# Schematic.net
KiCad netlist of a schematic drawn in EAGLE
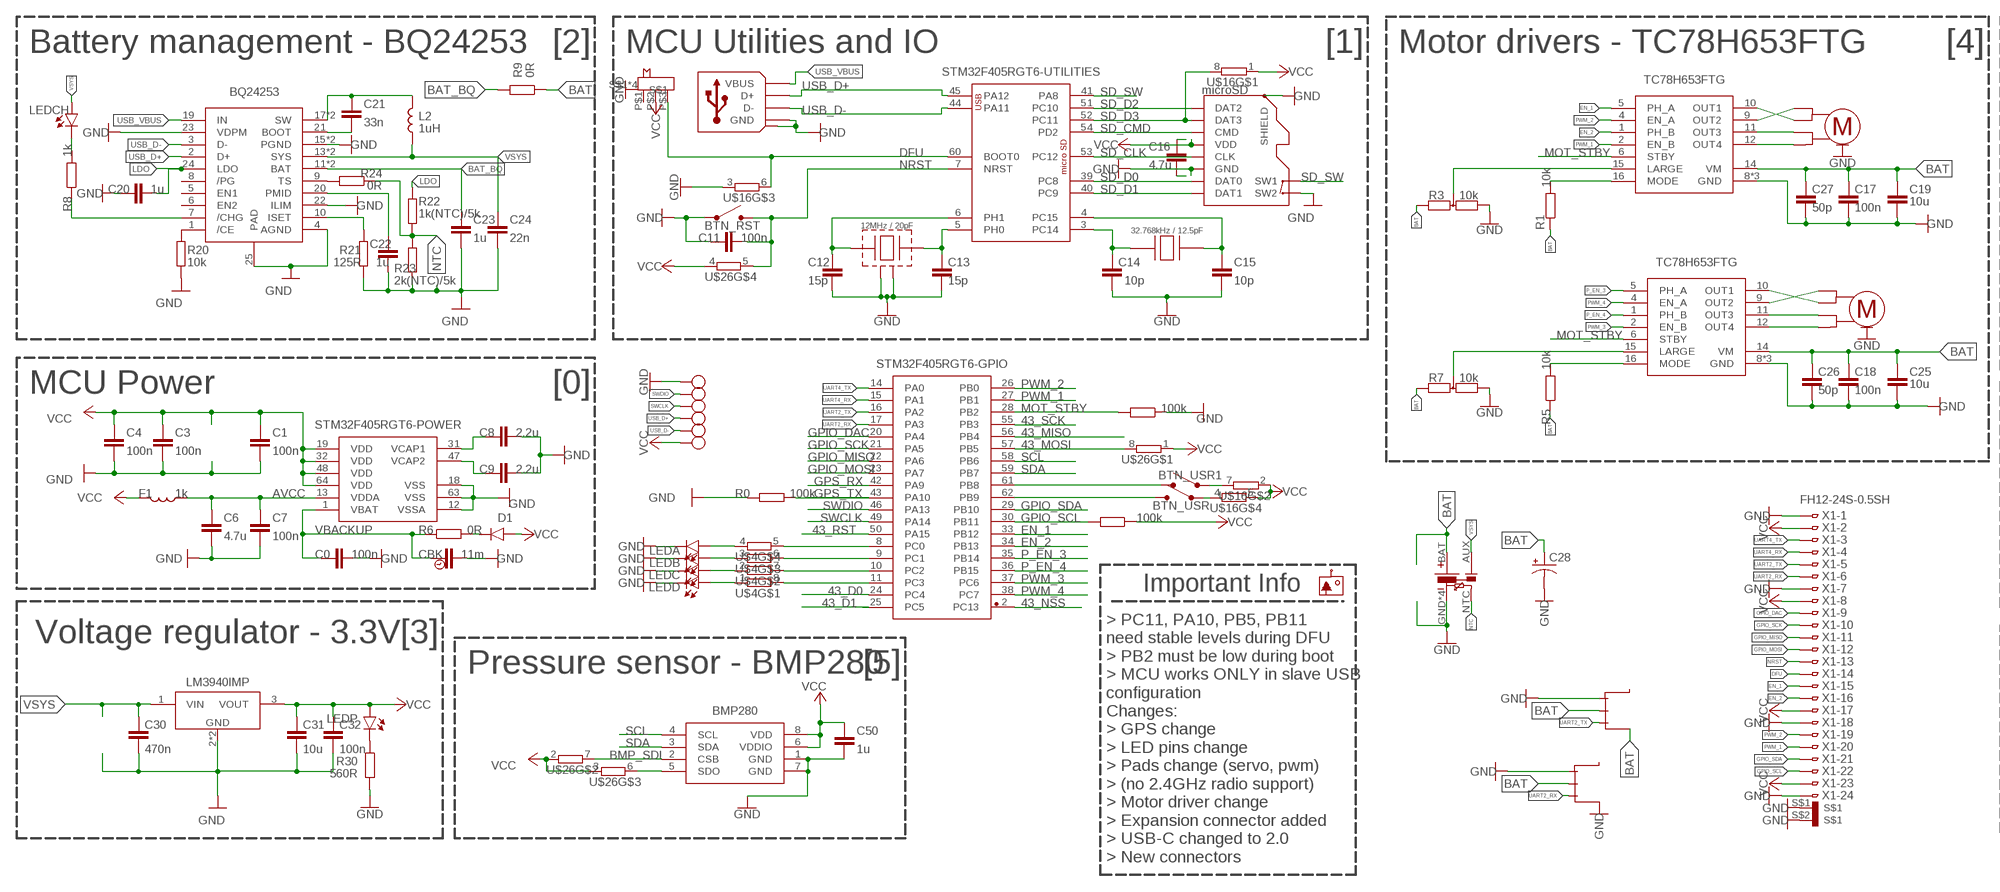
[diagram p0: schematic, sheet 1, part 1 of 2]
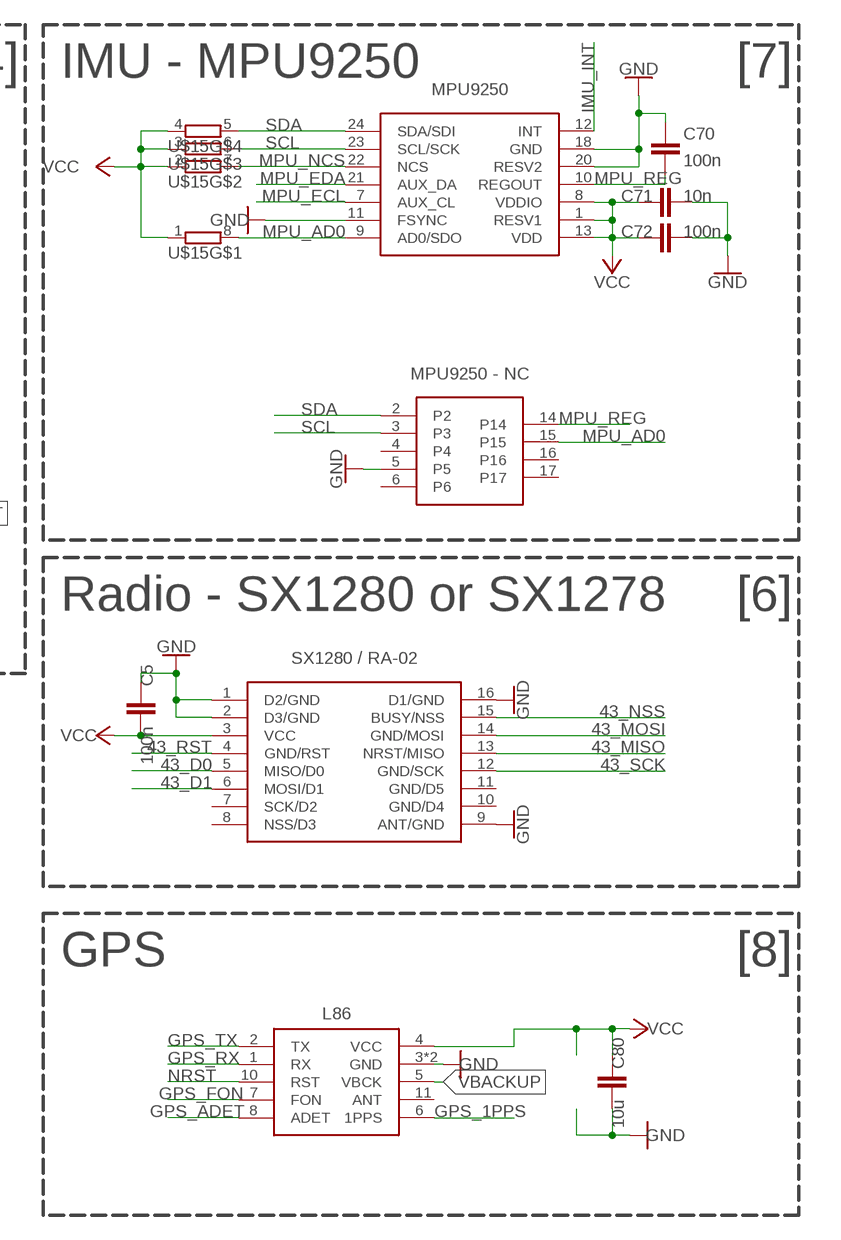
[diagram p1: schematic, sheet 1, part 2 of 2]

(export (version "E")
  (design (tool "Eeschema 10.0.6"))
  (components
    (comp (ref "BTN_DFU")
      (value "SLIDE-SWITCH2")
      (footprint "eagle-import:SLIDE-SWITCH-2")
      (libsource (lib "eagle-import") (part "SLIDE-SWITCH2"))
    )
    (comp (ref "BTN_RST")
      (value "PUSH-SWITCH")
      (footprint "eagle-import:SWITCH_SMD")
      (libsource (lib "eagle-import") (part "PUSH-SWITCH"))
    )
    (comp (ref "BTN_USR")
      (value "PUSH-SWITCH")
      (footprint "eagle-import:SWITCH_SMD")
      (libsource (lib "eagle-import") (part "PUSH-SWITCH"))
    )
    (comp (ref "BTN_USR1")
      (value "PUSH-SWITCH")
      (footprint "eagle-import:SWITCH_SMD")
      (libsource (lib "eagle-import") (part "PUSH-SWITCH"))
    )
    (comp (ref "C0")
      (value "100n")
      (footprint "eagle-import:C0603")
      (libsource (lib "eagle-import") (part "CAPACITOR0603"))
    )
    (comp (ref "C1")
      (value "100n")
      (footprint "eagle-import:C0603")
      (libsource (lib "eagle-import") (part "CAPACITOR0603"))
    )
    (comp (ref "C3")
      (value "100n")
      (footprint "eagle-import:C0603")
      (libsource (lib "eagle-import") (part "CAPACITOR0603"))
    )
    (comp (ref "C4")
      (value "100n")
      (footprint "eagle-import:C0603")
      (libsource (lib "eagle-import") (part "CAPACITOR0603"))
    )
    (comp (ref "C5")
      (value "100n")
      (footprint "eagle-import:C0603")
      (libsource (lib "eagle-import") (part "CAPACITOR0603"))
    )
    (comp (ref "C6")
      (value "4.7u")
      (footprint "eagle-import:C0603")
      (libsource (lib "eagle-import") (part "CAPACITOR0603"))
    )
    (comp (ref "C7")
      (value "100n")
      (footprint "eagle-import:C0603")
      (libsource (lib "eagle-import") (part "CAPACITOR0603"))
    )
    (comp (ref "C8")
      (value "2.2u")
      (footprint "eagle-import:C0603")
      (libsource (lib "eagle-import") (part "CAPACITOR0603"))
    )
    (comp (ref "C9")
      (value "2.2u")
      (footprint "eagle-import:C0603")
      (libsource (lib "eagle-import") (part "CAPACITOR0603"))
    )
    (comp (ref "C11")
      (value "100n")
      (footprint "eagle-import:C0603")
      (libsource (lib "eagle-import") (part "CAPACITOR0603"))
    )
    (comp (ref "C12")
      (value "15p")
      (footprint "eagle-import:C0603")
      (libsource (lib "eagle-import") (part "CAPACITOR0603"))
    )
    (comp (ref "C13")
      (value "15p")
      (footprint "eagle-import:C0603")
      (libsource (lib "eagle-import") (part "CAPACITOR0603"))
    )
    (comp (ref "C14")
      (value "10p")
      (footprint "eagle-import:C0603")
      (libsource (lib "eagle-import") (part "CAPACITOR0603"))
    )
    (comp (ref "C15")
      (value "10p")
      (footprint "eagle-import:C0603")
      (libsource (lib "eagle-import") (part "CAPACITOR0603"))
    )
    (comp (ref "C16")
      (value "4.7u")
      (footprint "eagle-import:C0603")
      (libsource (lib "eagle-import") (part "CAPACITOR0603"))
    )
    (comp (ref "C17")
      (value "100n")
      (footprint "eagle-import:C0603")
      (libsource (lib "eagle-import") (part "CAPACITOR0603"))
    )
    (comp (ref "C18")
      (value "100n")
      (footprint "eagle-import:C0603")
      (libsource (lib "eagle-import") (part "CAPACITOR0603"))
    )
    (comp (ref "C19")
      (value "10u")
      (footprint "eagle-import:C1206")
      (libsource (lib "eagle-import") (part "CAPACITOR1206"))
    )
    (comp (ref "C20")
      (value "1u")
      (footprint "eagle-import:C0603")
      (libsource (lib "eagle-import") (part "CAPACITOR0603"))
    )
    (comp (ref "C21")
      (value "33n")
      (footprint "eagle-import:C0603")
      (libsource (lib "eagle-import") (part "CAPACITOR0603"))
    )
    (comp (ref "C22")
      (value "1u")
      (footprint "eagle-import:C0603")
      (libsource (lib "eagle-import") (part "CAPACITOR0603"))
    )
    (comp (ref "C23")
      (value "1u")
      (footprint "eagle-import:C0603")
      (libsource (lib "eagle-import") (part "CAPACITOR0603"))
    )
    (comp (ref "C24")
      (value "22n")
      (footprint "eagle-import:C0603")
      (libsource (lib "eagle-import") (part "CAPACITOR0603"))
    )
    (comp (ref "C25")
      (value "10u")
      (footprint "eagle-import:C1206")
      (libsource (lib "eagle-import") (part "CAPACITOR1206"))
    )
    (comp (ref "C26")
      (value "50p")
      (footprint "eagle-import:C0603")
      (libsource (lib "eagle-import") (part "CAPACITOR0603"))
    )
    (comp (ref "C27")
      (value "50p")
      (footprint "eagle-import:C0603")
      (libsource (lib "eagle-import") (part "CAPACITOR0603"))
    )
    (comp (ref "C28")
      (value "CPOL-US153CLV-0405")
      (footprint "eagle-import:153CLV-0405")
      (libsource (lib "eagle-import") (part "CPOL-US153CLV-0405"))
    )
    (comp (ref "C30")
      (value "470n")
      (footprint "eagle-import:C0603")
      (libsource (lib "eagle-import") (part "CAPACITOR0603"))
    )
    (comp (ref "C31")
      (value "10u")
      (footprint "eagle-import:C1206")
      (libsource (lib "eagle-import") (part "CAPACITOR1206"))
    )
    (comp (ref "C32")
      (value "100n")
      (footprint "eagle-import:C0603")
      (libsource (lib "eagle-import") (part "CAPACITOR0603"))
    )
    (comp (ref "C50")
      (value "1u")
      (footprint "eagle-import:C0603")
      (libsource (lib "eagle-import") (part "CAPACITOR0603"))
    )
    (comp (ref "C70")
      (value "100n")
      (footprint "eagle-import:C0603")
      (libsource (lib "eagle-import") (part "CAPACITOR0603"))
    )
    (comp (ref "C71")
      (value "10n")
      (footprint "eagle-import:C0603")
      (libsource (lib "eagle-import") (part "CAPACITOR0603"))
    )
    (comp (ref "C72")
      (value "100n")
      (footprint "eagle-import:C0603")
      (libsource (lib "eagle-import") (part "CAPACITOR0603"))
    )
    (comp (ref "C80")
      (value "10u")
      (footprint "eagle-import:C0603")
      (libsource (lib "eagle-import") (part "CAPACITOR0603"))
    )
    (comp (ref "CBK")
      (value "11m")
      (footprint "eagle-import:CPH3225A")
      (libsource (lib "eagle-import") (part "SUPCAP"))
    )
    (comp (ref "D1")
      (value "DIODE")
      (footprint "eagle-import:R0603")
      (libsource (lib "eagle-import") (part "DIODE"))
    )
    (comp (ref "F1")
      (value "1k")
      (footprint "eagle-import:R0603")
      (libsource (lib "eagle-import") (part "INDUCTOR0603"))
    )
    (comp (ref "L2")
      (value "1uH")
      (footprint "eagle-import:INDUCTOR_VISHAY")
      (libsource (lib "eagle-import") (part "INDUCTOR"))
    )
    (comp (ref "LEDA")
      (value "LED0805")
      (footprint "eagle-import:CHIPLED_0805")
      (libsource (lib "eagle-import") (part "LED0805"))
    )
    (comp (ref "LEDB")
      (value "LED0805")
      (footprint "eagle-import:CHIPLED_0805")
      (libsource (lib "eagle-import") (part "LED0805"))
    )
    (comp (ref "LEDC")
      (value "LED0805")
      (footprint "eagle-import:CHIPLED_0805")
      (libsource (lib "eagle-import") (part "LED0805"))
    )
    (comp (ref "LEDCH")
      (value "LED0805")
      (footprint "eagle-import:CHIPLED_0805")
      (libsource (lib "eagle-import") (part "LED0805"))
    )
    (comp (ref "LEDD")
      (value "LED0805")
      (footprint "eagle-import:CHIPLED_0805")
      (libsource (lib "eagle-import") (part "LED0805"))
    )
    (comp (ref "LEDP")
      (value "LED0805")
      (footprint "eagle-import:CHIPLED_0805")
      (libsource (lib "eagle-import") (part "LED0805"))
    )
    (comp (ref "LM3940IMP")
      (value "REGULATOR")
      (footprint "eagle-import:SOT230P700X180-4N")
      (libsource (lib "eagle-import") (part "REGULATOR"))
    )
    (comp (ref "R0")
      (value "100k")
      (footprint "eagle-import:R0603")
      (libsource (lib "eagle-import") (part "RESISTOR0603"))
    )
    (comp (ref "R1")
      (value "10k")
      (footprint "eagle-import:R0603")
      (libsource (lib "eagle-import") (part "RESISTOR0603"))
    )
    (comp (ref "R2")
      (value "100k")
      (footprint "eagle-import:R0603")
      (libsource (lib "eagle-import") (part "RESISTOR0603"))
    )
    (comp (ref "R3")
      (value "10k")
      (footprint "eagle-import:DR0603")
      (libsource (lib "eagle-import") (part "DOUBLE_RESISTOR"))
    )
    (comp (ref "R4")
      (value "100k")
      (footprint "eagle-import:R0603")
      (libsource (lib "eagle-import") (part "RESISTOR0603"))
    )
    (comp (ref "R5")
      (value "10k")
      (footprint "eagle-import:R0603")
      (libsource (lib "eagle-import") (part "RESISTOR0603"))
    )
    (comp (ref "R6")
      (value "0R")
      (footprint "eagle-import:R0603")
      (libsource (lib "eagle-import") (part "RESISTOR0603"))
    )
    (comp (ref "R7")
      (value "10k")
      (footprint "eagle-import:DR0603")
      (libsource (lib "eagle-import") (part "DOUBLE_RESISTOR"))
    )
    (comp (ref "R8")
      (value "1k")
      (footprint "eagle-import:R0603")
      (libsource (lib "eagle-import") (part "RESISTOR0603"))
    )
    (comp (ref "R9")
      (value "0R")
      (footprint "eagle-import:R0603")
      (libsource (lib "eagle-import") (part "RESISTOR0603"))
    )
    (comp (ref "R20")
      (value "10k")
      (footprint "eagle-import:R0603")
      (libsource (lib "eagle-import") (part "RESISTOR0603"))
    )
    (comp (ref "R21")
      (value "125R")
      (footprint "eagle-import:R0603")
      (libsource (lib "eagle-import") (part "RESISTOR0603"))
    )
    (comp (ref "R22")
      (value "1k(NTC)/5k")
      (footprint "eagle-import:R0603")
      (libsource (lib "eagle-import") (part "RESISTOR0603"))
    )
    (comp (ref "R23")
      (value "2k(NTC)/5k")
      (footprint "eagle-import:R0603")
      (libsource (lib "eagle-import") (part "RESISTOR0603"))
    )
    (comp (ref "R24")
      (value "0R")
      (footprint "eagle-import:R0603")
      (libsource (lib "eagle-import") (part "RESISTOR0603"))
    )
    (comp (ref "R30")
      (value "560R")
      (footprint "eagle-import:R0603")
      (libsource (lib "eagle-import") (part "RESISTOR0603"))
    )
    (comp (ref "U$1")
      (value "STM32F405RGT6")
      (footprint "eagle-import:QFP50P1200X1200X160-64N")
      (libsource (lib "eagle-import") (part "STM32F405RGT6"))
    )
    (comp (ref "U$2")
      (value "MICROSD_HOLDER")
      (footprint "eagle-import:MICROSD_HOLDER")
      (libsource (lib "eagle-import") (part "MICROSD_HOLDER"))
    )
    (comp (ref "U$3")
      (value "L86")
      (footprint "eagle-import:L86")
      (libsource (lib "eagle-import") (part "L86"))
    )
    (comp (ref "U$4")
      (value "RESISTORARRAY")
      (footprint "eagle-import:0603-ARC")
      (libsource (lib "eagle-import") (part "RESISTORARRAY"))
    )
    (comp (ref "U$5")
      (value "32.768kHz / 12.5pF")
      (footprint "eagle-import:OSC32X15")
      (libsource (lib "eagle-import") (part "OSCILLATOR_2PIN32X15"))
    )
    (comp (ref "U$6")
      (value "12MHz / 20pF")
      (footprint "eagle-import:OSCCC320X250X80N")
      (libsource (lib "eagle-import") (part "OSCILLATOR_4PIN32X25"))
    )
    (comp (ref "U$7")
      (value "USB2.0")
      (footprint "eagle-import:USB-C(2)")
      (libsource (lib "eagle-import") (part "USB2.0"))
    )
    (comp (ref "U$8")
      (value "BMP280")
      (footprint "eagle-import:BMP280")
      (libsource (lib "eagle-import") (part "BMP280"))
    )
    (comp (ref "U$9")
      (value "MPU9250USR")
      (footprint "eagle-import:MPU9250")
      (libsource (lib "eagle-import") (part "MPU9250USR"))
    )
    (comp (ref "U$10")
      (value "BQ24253")
      (footprint "eagle-import:QFN50P400X400X100-25T270N")
      (libsource (lib "eagle-import") (part "BQ24253"))
    )
    (comp (ref "U$11")
      (value "TC78H653FTG")
      (footprint "eagle-import:QFN50P300X300X90-17T170N")
      (libsource (lib "eagle-import") (part "TC78H653FTG"))
    )
    (comp (ref "U$12")
      (value "TC78H653FTG")
      (footprint "eagle-import:QFN50P300X300X90-17T170N")
      (libsource (lib "eagle-import") (part "TC78H653FTG"))
    )
    (comp (ref "U$13")
      (value "MOTOR_DUO")
      (footprint "eagle-import:4(2)X_JSTSMD_F")
      (libsource (lib "eagle-import") (part "MOTOR_DUO"))
    )
    (comp (ref "U$14")
      (value "BAT_JST_4(3)")
      (footprint "eagle-import:4(3)X_JSTSMD_F")
      (libsource (lib "eagle-import") (part "BAT_JST_4(3)"))
    )
    (comp (ref "U$15")
      (value "RESISTORARRAY")
      (footprint "eagle-import:0603-ARC")
      (libsource (lib "eagle-import") (part "RESISTORARRAY"))
    )
    (comp (ref "U$16")
      (value "RESISTORARRAY")
      (footprint "eagle-import:0603-ARC")
      (libsource (lib "eagle-import") (part "RESISTORARRAY"))
    )
    (comp (ref "U$17")
      (value "MOTOR_DUO")
      (footprint "eagle-import:4(2)X_JSTSMD_F")
      (libsource (lib "eagle-import") (part "MOTOR_DUO"))
    )
    (comp (ref "U$18")
      (value "LOGOSQSM")
      (footprint "eagle-import:LOGOSQSM")
      (libsource (lib "eagle-import") (part "LOGOSQSM"))
    )
    (comp (ref "U$19")
      (value "CONNECTOR_F_X3_JST_SMD")
      (footprint "eagle-import:3X_JSTSMD_F")
      (libsource (lib "eagle-import") (part "CONNECTOR_F_X3_JST_SMD"))
    )
    (comp (ref "U$20")
      (value "CONNECTOR_F_X3_JST_SMD")
      (footprint "eagle-import:3X_JSTSMD_F")
      (libsource (lib "eagle-import") (part "CONNECTOR_F_X3_JST_SMD"))
    )
    (comp (ref "U$21")
      (value "LORADUO")
      (footprint "eagle-import:MODULE_SX1280")
      (libsource (lib "eagle-import") (part "LORADUO"))
    )
    (comp (ref "U$25")
      (value "GPIO_DEBUG")
      (footprint "eagle-import:GPIO_DEBUG")
      (libsource (lib "eagle-import") (part "GPIO_DEBUG"))
    )
    (comp (ref "U$26")
      (value "RESISTORARRAY")
      (footprint "eagle-import:0603-ARC")
      (libsource (lib "eagle-import") (part "RESISTORARRAY"))
    )
    (comp (ref "X1")
      (value "FH12-24S-0.5SH")
      (footprint "eagle-import:FH12-24S-0.5SH")
      (fields (field (name "MPN") "FH12-24S-0.5SH(55)"))
      (libsource (lib "eagle-import") (part "FH12-24S-0.5SH"))
    )
  )
  (nets
    (net (code "1") (name "/43_D0") (class "Default")
      (node (ref "U$1") (pin "24") (pinfunction "PC4_24") (pintype "bidirectional"))
      (node (ref "U$21") (pin "5") (pinfunction "MISO/D0_5") (pintype "bidirectional"))
    )
    (net (code "2") (name "/43_D1") (class "Default")
      (node (ref "U$1") (pin "25") (pinfunction "PC5_25") (pintype "bidirectional"))
      (node (ref "U$21") (pin "6") (pinfunction "MOSI/D1_6") (pintype "bidirectional"))
    )
    (net (code "3") (name "/43_MISO") (class "Default")
      (node (ref "U$1") (pin "56") (pinfunction "PB4_56") (pintype "bidirectional"))
      (node (ref "U$21") (pin "13") (pinfunction "NRST/MISO_13") (pintype "bidirectional"))
    )
    (net (code "4") (name "/43_MOSI") (class "Default")
      (node (ref "U$1") (pin "57") (pinfunction "PB5_57") (pintype "bidirectional"))
      (node (ref "U$21") (pin "14") (pinfunction "GND/MOSI_14") (pintype "bidirectional"))
      (node (ref "U$26") (pin "8") (pinfunction "2_8") (pintype "passive"))
    )
    (net (code "5") (name "/43_NSS") (class "Default")
      (node (ref "U$1") (pin "2") (pinfunction "PC13_2") (pintype "bidirectional"))
      (node (ref "U$21") (pin "15") (pinfunction "BUSY/NSS_15") (pintype "bidirectional"))
    )
    (net (code "6") (name "/43_RST") (class "Default")
      (node (ref "U$1") (pin "50") (pinfunction "PA15_50") (pintype "bidirectional"))
      (node (ref "U$21") (pin "4") (pinfunction "GND/RST_4") (pintype "bidirectional"))
    )
    (net (code "7") (name "/43_SCK") (class "Default")
      (node (ref "U$1") (pin "55") (pinfunction "PB3_55") (pintype "bidirectional"))
      (node (ref "U$21") (pin "12") (pinfunction "GND/SCK_12") (pintype "bidirectional"))
    )
    (net (code "8") (name "/AVCC") (class "Default")
      (node (ref "C6") (pin "1") (pinfunction "1_1") (pintype "passive"))
      (node (ref "C7") (pin "1") (pinfunction "1_1") (pintype "passive"))
      (node (ref "F1") (pin "2") (pinfunction "P$2_2") (pintype "bidirectional"))
      (node (ref "U$1") (pin "13") (pinfunction "VDDA_13") (pintype "bidirectional"))
    )
    (net (code "9") (name "/BMP_SDI") (class "Default")
      (node (ref "U$26") (pin "7") (pinfunction "2_7") (pintype "passive"))
      (node (ref "U$8") (pin "2") (pinfunction "CSB_2") (pintype "bidirectional"))
    )
    (net (code "10") (name "/GPS_1PPS") (class "Default")
      (node (ref "U$3") (pin "6") (pinfunction "1PPS_6") (pintype "bidirectional"))
    )
    (net (code "11") (name "/GPS_ADET") (class "Default")
      (node (ref "U$3") (pin "8") (pinfunction "ADET_8") (pintype "bidirectional"))
    )
    (net (code "12") (name "/GPS_FON") (class "Default")
      (node (ref "U$3") (pin "7") (pinfunction "FON_7") (pintype "bidirectional"))
    )
    (net (code "13") (name "/GPS_RX") (class "Default")
      (node (ref "U$1") (pin "42") (pinfunction "PA9_42") (pintype "bidirectional"))
      (node (ref "U$3") (pin "1") (pinfunction "RX_1") (pintype "bidirectional"))
    )
    (net (code "14") (name "/GPS_TX") (class "Default")
      (node (ref "R0") (pin "2") (pinfunction "2_2") (pintype "passive"))
      (node (ref "U$1") (pin "43") (pinfunction "PA10_43") (pintype "bidirectional"))
      (node (ref "U$3") (pin "2") (pinfunction "TX_2") (pintype "bidirectional"))
    )
    (net (code "15") (name "/IMU_INT") (class "Default")
      (node (ref "U$9") (pin "12") (pinfunction "INT_12") (pintype "bidirectional"))
    )
    (net (code "16") (name "/MOT_STBY") (class "Default")
      (node (ref "R2") (pin "2") (pinfunction "2_2") (pintype "passive"))
      (node (ref "U$1") (pin "28") (pinfunction "PB2_28") (pintype "bidirectional"))
      (node (ref "U$11") (pin "6") (pinfunction "STBY_6") (pintype "bidirectional"))
      (node (ref "U$12") (pin "6") (pinfunction "STBY_6") (pintype "bidirectional"))
    )
    (net (code "17") (name "/MPU_AD0") (class "Default")
      (node (ref "U$15") (pin "8") (pinfunction "2_8") (pintype "passive"))
      (node (ref "U$9") (pin "15") (pinfunction "P15_15") (pintype "bidirectional"))
      (node (ref "U$9") (pin "9") (pinfunction "AD0/SDO_9") (pintype "bidirectional"))
    )
    (net (code "18") (name "/MPU_ECL") (class "Default")
      (node (ref "U$9") (pin "7") (pinfunction "AUX_CL_7") (pintype "bidirectional"))
    )
    (net (code "19") (name "/MPU_EDA") (class "Default")
      (node (ref "U$9") (pin "21") (pinfunction "AUX_DA_21") (pintype "bidirectional"))
    )
    (net (code "20") (name "/MPU_NCS") (class "Default")
      (node (ref "U$15") (pin "7") (pinfunction "2_7") (pintype "passive"))
      (node (ref "U$9") (pin "22") (pinfunction "NCS_22") (pintype "bidirectional"))
    )
    (net (code "21") (name "/MPU_REG") (class "Default")
      (node (ref "C70") (pin "2") (pinfunction "2_2") (pintype "passive"))
      (node (ref "U$9") (pin "10") (pinfunction "REGOUT_10") (pintype "bidirectional"))
      (node (ref "U$9") (pin "14") (pinfunction "P14_14") (pintype "bidirectional"))
    )
    (net (code "22") (name "/SCL") (class "Default")
      (node (ref "U$1") (pin "58") (pinfunction "PB6_58") (pintype "bidirectional"))
      (node (ref "U$15") (pin "6") (pinfunction "2_6") (pintype "passive"))
      (node (ref "U$8") (pin "4") (pinfunction "SCL_4") (pintype "bidirectional"))
      (node (ref "U$9") (pin "23") (pinfunction "SCL/SCK_23") (pintype "bidirectional"))
      (node (ref "U$9") (pin "3") (pinfunction "P3_3") (pintype "bidirectional"))
    )
    (net (code "23") (name "/SDA") (class "Default")
      (node (ref "U$1") (pin "59") (pinfunction "PB7_59") (pintype "bidirectional"))
      (node (ref "U$15") (pin "5") (pinfunction "2_5") (pintype "passive"))
      (node (ref "U$8") (pin "3") (pinfunction "SDA_3") (pintype "bidirectional"))
      (node (ref "U$9") (pin "2") (pinfunction "P2_2") (pintype "bidirectional"))
      (node (ref "U$9") (pin "24") (pinfunction "SDA/SDI_24") (pintype "bidirectional"))
    )
    (net (code "24") (name "/SD_CLK") (class "Default")
      (node (ref "U$1") (pin "53") (pinfunction "PC12_53") (pintype "bidirectional"))
      (node (ref "U$2") (pin "CLK") (pinfunction "CLK_CLK") (pintype "bidirectional"))
    )
    (net (code "25") (name "/SD_CMD") (class "Default")
      (node (ref "U$1") (pin "54") (pinfunction "PD2_54") (pintype "bidirectional"))
      (node (ref "U$2") (pin "CMD") (pinfunction "CMD_CMD") (pintype "bidirectional"))
    )
    (net (code "26") (name "/SD_D0") (class "Default")
      (node (ref "U$1") (pin "39") (pinfunction "PC8_39") (pintype "bidirectional"))
      (node (ref "U$2") (pin "D0") (pinfunction "DAT0_D0") (pintype "bidirectional"))
    )
    (net (code "27") (name "/SD_D1") (class "Default")
      (node (ref "U$1") (pin "40") (pinfunction "PC9_40") (pintype "bidirectional"))
      (node (ref "U$2") (pin "D1") (pinfunction "DAT1_D1") (pintype "bidirectional"))
    )
    (net (code "28") (name "/SD_D2") (class "Default")
      (node (ref "U$1") (pin "51") (pinfunction "PC10_51") (pintype "bidirectional"))
      (node (ref "U$2") (pin "D2") (pinfunction "DAT2_D2") (pintype "bidirectional"))
    )
    (net (code "29") (name "/SD_D3") (class "Default")
      (node (ref "U$1") (pin "52") (pinfunction "PC11_52") (pintype "bidirectional"))
      (node (ref "U$16") (pin "8") (pinfunction "2_8") (pintype "passive"))
      (node (ref "U$2") (pin "D3") (pinfunction "DAT3_D3") (pintype "bidirectional"))
    )
    (net (code "30") (name "/SD_SW") (class "Default")
      (node (ref "U$1") (pin "41") (pinfunction "PA8_41") (pintype "bidirectional"))
      (node (ref "U$2") (pin "SW1") (pinfunction "SW1_SW1") (pintype "bidirectional"))
    )
    (net (code "31") (name "BAT") (class "Default")
      (node (ref "C17") (pin "1") (pinfunction "1_1") (pintype "passive"))
      (node (ref "C18") (pin "1") (pinfunction "1_1") (pintype "passive"))
      (node (ref "C19") (pin "1") (pinfunction "1_1") (pintype "passive"))
      (node (ref "C25") (pin "1") (pinfunction "1_1") (pintype "passive"))
      (node (ref "C26") (pin "1") (pinfunction "1_1") (pintype "passive"))
      (node (ref "C27") (pin "1") (pinfunction "1_1") (pintype "passive"))
      (node (ref "C28") (pin "+") (pinfunction "+_+") (pintype "passive"))
      (node (ref "R1") (pin "1") (pinfunction "1_1") (pintype "passive"))
      (node (ref "R3") (pin "2") (pinfunction "P$2_2") (pintype "bidirectional"))
      (node (ref "R5") (pin "1") (pinfunction "1_1") (pintype "passive"))
      (node (ref "R7") (pin "2") (pinfunction "P$2_2") (pintype "bidirectional"))
      (node (ref "R9") (pin "1") (pinfunction "1_1") (pintype "passive"))
      (node (ref "U$11") (pin "14") (pinfunction "VM_14") (pintype "bidirectional"))
      (node (ref "U$12") (pin "14") (pinfunction "VM_14") (pintype "bidirectional"))
      (node (ref "U$14") (pin "BAT") (pinfunction "+_BAT") (pintype "bidirectional"))
      (node (ref "U$19") (pin "P$2") (pinfunction "P$2_P$2") (pintype "bidirectional"))
      (node (ref "U$19") (pin "S$1") (pinfunction "S$1_S$1") (pintype "bidirectional"))
      (node (ref "U$19") (pin "S$2") (pinfunction "S$1_S$2") (pintype "bidirectional"))
      (node (ref "U$20") (pin "P$2") (pinfunction "P$2_P$2") (pintype "bidirectional"))
    )
    (net (code "32") (name "BAT_BQ") (class "Default")
      (node (ref "C23") (pin "1") (pinfunction "1_1") (pintype "passive"))
      (node (ref "R9") (pin "2") (pinfunction "2_2") (pintype "passive"))
      (node (ref "U$10") (pin "11") (pinfunction "BAT_11") (pintype "bidirectional"))
      (node (ref "U$10") (pin "12") (pinfunction "BAT_12") (pintype "bidirectional"))
    )
    (net (code "33") (name "DFU") (class "Default")
      (node (ref "BTN_DFU") (pin "P$3") (pinfunction "P$3_P$3") (pintype "bidirectional"))
      (node (ref "U$1") (pin "60") (pinfunction "BOOT0_60") (pintype "bidirectional"))
      (node (ref "U$16") (pin "6") (pinfunction "2_6") (pintype "passive"))
      (node (ref "X1") (pin "14") (pinfunction "1_14") (pintype "passive"))
    )
    (net (code "34") (name "EN_1") (class "Default")
      (node (ref "U$1") (pin "33") (pinfunction "PB12_33") (pintype "bidirectional"))
      (node (ref "U$12") (pin "5") (pinfunction "PH_A_5") (pintype "bidirectional"))
      (node (ref "X1") (pin "15") (pinfunction "1_15") (pintype "passive"))
    )
    (net (code "35") (name "EN_2") (class "Default")
      (node (ref "U$1") (pin "34") (pinfunction "PB13_34") (pintype "bidirectional"))
      (node (ref "U$12") (pin "1") (pinfunction "PH_B_1") (pintype "bidirectional"))
      (node (ref "X1") (pin "16") (pinfunction "1_16") (pintype "passive"))
    )
    (net (code "36") (name "GND") (class "Default")
      (node (ref "BTN_DFU") (pin "S$1") (pinfunction "S$1_S$1") (pintype "bidirectional"))
      (node (ref "BTN_DFU") (pin "S$2") (pinfunction "S$1_S$2") (pintype "bidirectional"))
      (node (ref "BTN_DFU") (pin "S$3") (pinfunction "S$1_S$3") (pintype "bidirectional"))
      (node (ref "BTN_DFU") (pin "S$4") (pinfunction "S$1_S$4") (pintype "bidirectional"))
      (node (ref "BTN_RST") (pin "P$1") (pinfunction "P$1_P$1") (pintype "bidirectional"))
      (node (ref "BTN_RST") (pin "P$4") (pinfunction "P$1_P$4") (pintype "bidirectional"))
      (node (ref "C0") (pin "2") (pinfunction "2_2") (pintype "passive"))
      (node (ref "C1") (pin "2") (pinfunction "2_2") (pintype "passive"))
      (node (ref "C11") (pin "1") (pinfunction "1_1") (pintype "passive"))
      (node (ref "C12") (pin "2") (pinfunction "2_2") (pintype "passive"))
      (node (ref "C13") (pin "2") (pinfunction "2_2") (pintype "passive"))
      (node (ref "C14") (pin "2") (pinfunction "2_2") (pintype "passive"))
      (node (ref "C15") (pin "2") (pinfunction "2_2") (pintype "passive"))
      (node (ref "C16") (pin "1") (pinfunction "1_1") (pintype "passive"))
      (node (ref "C17") (pin "2") (pinfunction "2_2") (pintype "passive"))
      (node (ref "C18") (pin "2") (pinfunction "2_2") (pintype "passive"))
      (node (ref "C19") (pin "2") (pinfunction "2_2") (pintype "passive"))
      (node (ref "C20") (pin "1") (pinfunction "1_1") (pintype "passive"))
      (node (ref "C22") (pin "2") (pinfunction "2_2") (pintype "passive"))
      (node (ref "C23") (pin "2") (pinfunction "2_2") (pintype "passive"))
      (node (ref "C24") (pin "2") (pinfunction "2_2") (pintype "passive"))
      (node (ref "C25") (pin "2") (pinfunction "2_2") (pintype "passive"))
      (node (ref "C26") (pin "2") (pinfunction "2_2") (pintype "passive"))
      (node (ref "C27") (pin "2") (pinfunction "2_2") (pintype "passive"))
      (node (ref "C28") (pin "-") (pinfunction "-_-") (pintype "passive"))
      (node (ref "C3") (pin "2") (pinfunction "2_2") (pintype "passive"))
      (node (ref "C30") (pin "2") (pinfunction "2_2") (pintype "passive"))
      (node (ref "C31") (pin "2") (pinfunction "2_2") (pintype "passive"))
      (node (ref "C32") (pin "2") (pinfunction "2_2") (pintype "passive"))
      (node (ref "C4") (pin "2") (pinfunction "2_2") (pintype "passive"))
      (node (ref "C5") (pin "1") (pinfunction "1_1") (pintype "passive"))
      (node (ref "C50") (pin "2") (pinfunction "2_2") (pintype "passive"))
      (node (ref "C6") (pin "2") (pinfunction "2_2") (pintype "passive"))
      (node (ref "C7") (pin "2") (pinfunction "2_2") (pintype "passive"))
      (node (ref "C70") (pin "1") (pinfunction "1_1") (pintype "passive"))
      (node (ref "C71") (pin "2") (pinfunction "2_2") (pintype "passive"))
      (node (ref "C72") (pin "2") (pinfunction "2_2") (pintype "passive"))
      (node (ref "C8") (pin "2") (pinfunction "2_2") (pintype "passive"))
      (node (ref "C80") (pin "2") (pinfunction "2_2") (pintype "passive"))
      (node (ref "C9") (pin "2") (pinfunction "2_2") (pintype "passive"))
      (node (ref "CBK") (pin "P$2") (pinfunction "2_P$2") (pintype "passive"))
      (node (ref "LEDA") (pin "C") (pinfunction "P$2_C") (pintype "bidirectional"))
      (node (ref "LEDB") (pin "C") (pinfunction "P$2_C") (pintype "bidirectional"))
      (node (ref "LEDC") (pin "C") (pinfunction "P$2_C") (pintype "bidirectional"))
      (node (ref "LEDD") (pin "C") (pinfunction "P$2_C") (pintype "bidirectional"))
      (node (ref "LM3940IMP") (pin "2") (pinfunction "GND_2") (pintype "bidirectional"))
      (node (ref "LM3940IMP") (pin "4") (pinfunction "GND_4") (pintype "bidirectional"))
      (node (ref "R0") (pin "1") (pinfunction "1_1") (pintype "passive"))
      (node (ref "R2") (pin "1") (pinfunction "1_1") (pintype "passive"))
      (node (ref "R20") (pin "1") (pinfunction "1_1") (pintype "passive"))
      (node (ref "R21") (pin "1") (pinfunction "1_1") (pintype "passive"))
      (node (ref "R23") (pin "1") (pinfunction "1_1") (pintype "passive"))
      (node (ref "R3") (pin "3") (pinfunction "P$3_3") (pintype "bidirectional"))
      (node (ref "R30") (pin "2") (pinfunction "2_2") (pintype "passive"))
      (node (ref "R7") (pin "3") (pinfunction "P$3_3") (pintype "bidirectional"))
      (node (ref "U$1") (pin "12") (pinfunction "VSSA_12") (pintype "bidirectional"))
      (node (ref "U$1") (pin "18") (pinfunction "VSS_18") (pintype "bidirectional"))
      (node (ref "U$1") (pin "63") (pinfunction "VSS_63") (pintype "bidirectional"))
      (node (ref "U$10") (pin "15") (pinfunction "PGND_15") (pintype "bidirectional"))
      (node (ref "U$10") (pin "16") (pinfunction "PGND_16") (pintype "bidirectional"))
      (node (ref "U$10") (pin "22") (pinfunction "ILIM_22") (pintype "bidirectional"))
      (node (ref "U$10") (pin "23") (pinfunction "VDPM_23") (pintype "bidirectional"))
      (node (ref "U$10") (pin "25") (pinfunction "PAD_25") (pintype "bidirectional"))
      (node (ref "U$10") (pin "4") (pinfunction "AGND_4") (pintype "bidirectional"))
      (node (ref "U$11") (pin "13") (pinfunction "GND_13") (pintype "bidirectional"))
      (node (ref "U$11") (pin "17") (pinfunction "GND_17") (pintype "bidirectional"))
      (node (ref "U$11") (pin "8") (pinfunction "GND_8") (pintype "bidirectional"))
      (node (ref "U$12") (pin "13") (pinfunction "GND_13") (pintype "bidirectional"))
      (node (ref "U$12") (pin "17") (pinfunction "GND_17") (pintype "bidirectional"))
      (node (ref "U$12") (pin "8") (pinfunction "GND_8") (pintype "bidirectional"))
      (node (ref "U$13") (pin "S$1") (pinfunction "S$1_S$1") (pintype "bidirectional"))
      (node (ref "U$13") (pin "S$2") (pinfunction "S$1_S$2") (pintype "bidirectional"))
      (node (ref "U$13") (pin "S$3") (pinfunction "S$1_S$3") (pintype "bidirectional"))
      (node (ref "U$13") (pin "S$4") (pinfunction "S$1_S$4") (pintype "bidirectional"))
      (node (ref "U$14") (pin "GND") (pinfunction "-_GND") (pintype "bidirectional"))
      (node (ref "U$14") (pin "S$1") (pinfunction "-_S$1") (pintype "bidirectional"))
      (node (ref "U$14") (pin "S$2") (pinfunction "-_S$2") (pintype "bidirectional"))
      (node (ref "U$14") (pin "S$3") (pinfunction "-_S$3") (pintype "bidirectional"))
      (node (ref "U$16") (pin "3") (pinfunction "1_3") (pintype "passive"))
      (node (ref "U$17") (pin "S$1") (pinfunction "S$1_S$1") (pintype "bidirectional"))
      (node (ref "U$17") (pin "S$2") (pinfunction "S$1_S$2") (pintype "bidirectional"))
      (node (ref "U$17") (pin "S$3") (pinfunction "S$1_S$3") (pintype "bidirectional"))
      (node (ref "U$17") (pin "S$4") (pinfunction "S$1_S$4") (pintype "bidirectional"))
      (node (ref "U$19") (pin "P$1") (pinfunction "P$1_P$1") (pintype "bidirectional"))
      (node (ref "U$2") (pin "GND") (pinfunction "GND_GND") (pintype "bidirectional"))
      (node (ref "U$2") (pin "SHIELD@1") (pinfunction "SHIELD_SHIELD@1") (pintype "bidirectional"))
      (node (ref "U$2") (pin "SHIELD@2") (pinfunction "SHIELD_SHIELD@2") (pintype "bidirectional"))
      (node (ref "U$2") (pin "SHIELD@3") (pinfunction "SHIELD_SHIELD@3") (pintype "bidirectional"))
      (node (ref "U$2") (pin "SHIELD@4") (pinfunction "SHIELD_SHIELD@4") (pintype "bidirectional"))
      (node (ref "U$2") (pin "SW2") (pinfunction "SW2_SW2") (pintype "bidirectional"))
      (node (ref "U$20") (pin "P$1") (pinfunction "P$1_P$1") (pintype "bidirectional"))
      (node (ref "U$20") (pin "S$1") (pinfunction "S$1_S$1") (pintype "bidirectional"))
      (node (ref "U$20") (pin "S$2") (pinfunction "S$1_S$2") (pintype "bidirectional"))
      (node (ref "U$21") (pin "1") (pinfunction "D2/GND_1") (pintype "bidirectional"))
      (node (ref "U$21") (pin "16") (pinfunction "D1/GND_16") (pintype "bidirectional"))
      (node (ref "U$21") (pin "2") (pinfunction "D3/GND_2") (pintype "bidirectional"))
      (node (ref "U$21") (pin "9") (pinfunction "ANT/GND_9") (pintype "bidirectional"))
      (node (ref "U$25") (pin "P$1") (pinfunction "P$1_P$1") (pintype "bidirectional"))
      (node (ref "U$3") (pin "12") (pinfunction "GND_12") (pintype "bidirectional"))
      (node (ref "U$3") (pin "3") (pinfunction "GND_3") (pintype "bidirectional"))
      (node (ref "U$6") (pin "2") (pinfunction "GND_2") (pintype "bidirectional"))
      (node (ref "U$6") (pin "4") (pinfunction "GND_4") (pintype "bidirectional"))
      (node (ref "U$7") (pin "A1") (pinfunction "GND_A1") (pintype "bidirectional"))
      (node (ref "U$7") (pin "A12") (pinfunction "GND_A12") (pintype "bidirectional"))
      (node (ref "U$7") (pin "B1") (pinfunction "GND_B1") (pintype "bidirectional"))
      (node (ref "U$7") (pin "B12") (pinfunction "GND_B12") (pintype "bidirectional"))
      (node (ref "U$7") (pin "MID@1") (pinfunction "SHIELD_MID@1") (pintype "bidirectional"))
      (node (ref "U$7") (pin "MID@2") (pinfunction "SHIELD_MID@2") (pintype "bidirectional"))
      (node (ref "U$7") (pin "S$1") (pinfunction "GND_S$1") (pintype "bidirectional"))
      (node (ref "U$7") (pin "S$2") (pinfunction "GND_S$2") (pintype "bidirectional"))
      (node (ref "U$7") (pin "S$3") (pinfunction "GND_S$3") (pintype "bidirectional"))
      (node (ref "U$7") (pin "S$4") (pinfunction "GND_S$4") (pintype "bidirectional"))
      (node (ref "U$7") (pin "S$5") (pinfunction "GND_S$5") (pintype "bidirectional"))
      (node (ref "U$7") (pin "S$6") (pinfunction "GND_S$6") (pintype "bidirectional"))
      (node (ref "U$7") (pin "S$7") (pinfunction "GND_S$7") (pintype "bidirectional"))
      (node (ref "U$7") (pin "S$8") (pinfunction "GND_S$8") (pintype "bidirectional"))
      (node (ref "U$8") (pin "1") (pinfunction "GND_1") (pintype "bidirectional"))
      (node (ref "U$8") (pin "7") (pinfunction "GND_7") (pintype "bidirectional"))
      (node (ref "U$9") (pin "11") (pinfunction "FSYNC_11") (pintype "bidirectional"))
      (node (ref "U$9") (pin "18") (pinfunction "GND_18") (pintype "bidirectional"))
      (node (ref "U$9") (pin "20") (pinfunction "RESV2_20") (pintype "bidirectional"))
      (node (ref "U$9") (pin "5") (pinfunction "P5_5") (pintype "bidirectional"))
      (node (ref "X1") (pin "1") (pinfunction "1_1") (pintype "passive"))
      (node (ref "X1") (pin "18") (pinfunction "1_18") (pintype "passive"))
      (node (ref "X1") (pin "24") (pinfunction "1_24") (pintype "passive"))
      (node (ref "X1") (pin "7") (pinfunction "1_7") (pintype "passive"))
      (node (ref "X1") (pin "S$1") (pinfunction "S$1_S$1") (pintype "bidirectional"))
      (node (ref "X1") (pin "S$2") (pinfunction "S$1_S$2") (pintype "bidirectional"))
    )
    (net (code "37") (name "GPIO_DAC") (class "Default")
      (node (ref "U$1") (pin "20") (pinfunction "PA4_20") (pintype "bidirectional"))
      (node (ref "X1") (pin "9") (pinfunction "1_9") (pintype "passive"))
    )
    (net (code "38") (name "GPIO_MISO") (class "Default")
      (node (ref "U$1") (pin "22") (pinfunction "PA6_22") (pintype "bidirectional"))
      (node (ref "X1") (pin "11") (pinfunction "1_11") (pintype "passive"))
    )
    (net (code "39") (name "GPIO_MOSI") (class "Default")
      (node (ref "U$1") (pin "23") (pinfunction "PA7_23") (pintype "bidirectional"))
      (node (ref "X1") (pin "12") (pinfunction "1_12") (pintype "passive"))
    )
    (net (code "40") (name "GPIO_SCK") (class "Default")
      (node (ref "U$1") (pin "21") (pinfunction "PA5_21") (pintype "bidirectional"))
      (node (ref "X1") (pin "10") (pinfunction "1_10") (pintype "passive"))
    )
    (net (code "41") (name "GPIO_SCL") (class "Default")
      (node (ref "R4") (pin "2") (pinfunction "2_2") (pintype "passive"))
      (node (ref "U$1") (pin "30") (pinfunction "PB11_30") (pintype "bidirectional"))
      (node (ref "X1") (pin "22") (pinfunction "1_22") (pintype "passive"))
    )
    (net (code "42") (name "GPIO_SDA") (class "Default")
      (node (ref "U$1") (pin "29") (pinfunction "PB10_29") (pintype "bidirectional"))
      (node (ref "X1") (pin "21") (pinfunction "1_21") (pintype "passive"))
    )
    (net (code "43") (name "LDO") (class "Default")
      (node (ref "C20") (pin "2") (pinfunction "2_2") (pintype "passive"))
      (node (ref "R22") (pin "2") (pinfunction "2_2") (pintype "passive"))
      (node (ref "U$10") (pin "24") (pinfunction "LDO_24") (pintype "bidirectional"))
    )
    (net (code "44") (name "NRST") (class "Default")
      (node (ref "BTN_RST") (pin "P$2") (pinfunction "P$2_P$2") (pintype "bidirectional"))
      (node (ref "BTN_RST") (pin "P$3") (pinfunction "P$2_P$3") (pintype "bidirectional"))
      (node (ref "C11") (pin "2") (pinfunction "2_2") (pintype "passive"))
      (node (ref "U$1") (pin "7") (pinfunction "NRST_7") (pintype "bidirectional"))
      (node (ref "U$26") (pin "5") (pinfunction "2_5") (pintype "passive"))
      (node (ref "U$3") (pin "10") (pinfunction "RST_10") (pintype "bidirectional"))
      (node (ref "X1") (pin "13") (pinfunction "1_13") (pintype "passive"))
    )
    (net (code "45") (name "NTC") (class "Default")
      (node (ref "R22") (pin "1") (pinfunction "1_1") (pintype "passive"))
      (node (ref "R23") (pin "2") (pinfunction "2_2") (pintype "passive"))
      (node (ref "R24") (pin "1") (pinfunction "1_1") (pintype "passive"))
      (node (ref "U$14") (pin "NTC") (pinfunction "NTC_NTC") (pintype "bidirectional"))
    )
    (net (code "46") (name "Net-(C21-Pad1)") (class "Default")
      (node (ref "C21") (pin "1") (pinfunction "1_1") (pintype "passive"))
      (node (ref "L2") (pin "P$1") (pinfunction "P$1_P$1") (pintype "bidirectional"))
      (node (ref "U$10") (pin "17") (pinfunction "SW_17") (pintype "bidirectional"))
      (node (ref "U$10") (pin "18") (pinfunction "SW_18") (pintype "bidirectional"))
    )
    (net (code "47") (name "Net-(D1-P$2)") (class "Default")
      (node (ref "D1") (pin "2") (pinfunction "P$2_2") (pintype "bidirectional"))
      (node (ref "R6") (pin "2") (pinfunction "2_2") (pintype "passive"))
    )
    (net (code "48") (name "Net-(LEDA-P$1)") (class "Default")
      (node (ref "LEDA") (pin "A") (pinfunction "P$1_A") (pintype "bidirectional"))
      (node (ref "U$4") (pin "4") (pinfunction "1_4") (pintype "passive"))
    )
    (net (code "49") (name "Net-(LEDB-P$1)") (class "Default")
      (node (ref "LEDB") (pin "A") (pinfunction "P$1_A") (pintype "bidirectional"))
      (node (ref "U$4") (pin "3") (pinfunction "1_3") (pintype "passive"))
    )
    (net (code "50") (name "Net-(LEDC-P$1)") (class "Default")
      (node (ref "LEDC") (pin "A") (pinfunction "P$1_A") (pintype "bidirectional"))
      (node (ref "U$4") (pin "2") (pinfunction "1_2") (pintype "passive"))
    )
    (net (code "51") (name "Net-(LEDCH-P$2)") (class "Default")
      (node (ref "LEDCH") (pin "C") (pinfunction "P$2_C") (pintype "bidirectional"))
      (node (ref "R8") (pin "2") (pinfunction "2_2") (pintype "passive"))
    )
    (net (code "52") (name "Net-(LEDD-P$1)") (class "Default")
      (node (ref "LEDD") (pin "A") (pinfunction "P$1_A") (pintype "bidirectional"))
      (node (ref "U$4") (pin "1") (pinfunction "1_1") (pintype "passive"))
    )
    (net (code "53") (name "Net-(LEDP-P$2)") (class "Default")
      (node (ref "LEDP") (pin "C") (pinfunction "P$2_C") (pintype "bidirectional"))
      (node (ref "R30") (pin "1") (pinfunction "1_1") (pintype "passive"))
    )
    (net (code "54") (name "Net-(R3-P$1)") (class "Default")
      (node (ref "R3") (pin "1") (pinfunction "P$1_1") (pintype "bidirectional"))
      (node (ref "U$12") (pin "15") (pinfunction "LARGE_15") (pintype "bidirectional"))
    )
    (net (code "55") (name "Net-(R7-P$1)") (class "Default")
      (node (ref "R7") (pin "1") (pinfunction "P$1_1") (pintype "bidirectional"))
      (node (ref "U$11") (pin "15") (pinfunction "LARGE_15") (pintype "bidirectional"))
    )
    (net (code "56") (name "Net-(U$1A-PB8)") (class "Default")
      (node (ref "BTN_USR1") (pin "P$2") (pinfunction "P$2_P$2") (pintype "bidirectional"))
      (node (ref "BTN_USR1") (pin "P$3") (pinfunction "P$2_P$3") (pintype "bidirectional"))
      (node (ref "U$1") (pin "61") (pinfunction "PB8_61") (pintype "bidirectional"))
    )
    (net (code "57") (name "Net-(U$1A-PB9)") (class "Default")
      (node (ref "BTN_USR") (pin "P$2") (pinfunction "P$2_P$2") (pintype "bidirectional"))
      (node (ref "BTN_USR") (pin "P$3") (pinfunction "P$2_P$3") (pintype "bidirectional"))
      (node (ref "U$1") (pin "62") (pinfunction "PB9_62") (pintype "bidirectional"))
    )
    (net (code "58") (name "Net-(U$1A-PC0)") (class "Default")
      (node (ref "U$1") (pin "8") (pinfunction "PC0_8") (pintype "bidirectional"))
      (node (ref "U$4") (pin "5") (pinfunction "2_5") (pintype "passive"))
    )
    (net (code "59") (name "Net-(U$1A-PC1)") (class "Default")
      (node (ref "U$1") (pin "9") (pinfunction "PC1_9") (pintype "bidirectional"))
      (node (ref "U$4") (pin "6") (pinfunction "2_6") (pintype "passive"))
    )
    (net (code "60") (name "Net-(U$1A-PC2)") (class "Default")
      (node (ref "U$1") (pin "10") (pinfunction "PC2_10") (pintype "bidirectional"))
      (node (ref "U$4") (pin "7") (pinfunction "2_7") (pintype "passive"))
    )
    (net (code "61") (name "Net-(U$1A-PC3)") (class "Default")
      (node (ref "U$1") (pin "11") (pinfunction "PC3_11") (pintype "bidirectional"))
      (node (ref "U$4") (pin "8") (pinfunction "2_8") (pintype "passive"))
    )
    (net (code "62") (name "Net-(U$1B-VCAP1)") (class "Default")
      (node (ref "C8") (pin "1") (pinfunction "1_1") (pintype "passive"))
      (node (ref "U$1") (pin "31") (pinfunction "VCAP1_31") (pintype "bidirectional"))
    )
    (net (code "63") (name "Net-(U$1B-VCAP2)") (class "Default")
      (node (ref "C9") (pin "1") (pinfunction "1_1") (pintype "passive"))
      (node (ref "U$1") (pin "47") (pinfunction "VCAP2_47") (pintype "bidirectional"))
    )
    (net (code "64") (name "Net-(U$1C-PC14)") (class "Default")
      (node (ref "C14") (pin "1") (pinfunction "1_1") (pintype "passive"))
      (node (ref "U$1") (pin "3") (pinfunction "PC14_3") (pintype "bidirectional"))
      (node (ref "U$5") (pin "P$1") (pinfunction "P$1_P$1") (pintype "bidirectional"))
    )
    (net (code "65") (name "Net-(U$1C-PC15)") (class "Default")
      (node (ref "C15") (pin "1") (pinfunction "1_1") (pintype "passive"))
      (node (ref "U$1") (pin "4") (pinfunction "PC15_4") (pintype "bidirectional"))
      (node (ref "U$5") (pin "P$2") (pinfunction "P$2_P$2") (pintype "bidirectional"))
    )
    (net (code "66") (name "Net-(U$1C-PH0)") (class "Default")
      (node (ref "C13") (pin "1") (pinfunction "1_1") (pintype "passive"))
      (node (ref "U$1") (pin "5") (pinfunction "PH0_5") (pintype "bidirectional"))
      (node (ref "U$6") (pin "3") (pinfunction "P$2_3") (pintype "bidirectional"))
    )
    (net (code "67") (name "Net-(U$1C-PH1)") (class "Default")
      (node (ref "C12") (pin "1") (pinfunction "1_1") (pintype "passive"))
      (node (ref "U$1") (pin "6") (pinfunction "PH1_6") (pintype "bidirectional"))
      (node (ref "U$6") (pin "1") (pinfunction "P$1_1") (pintype "bidirectional"))
    )
    (net (code "68") (name "Net-(U$10-BOOT)") (class "Default")
      (node (ref "C21") (pin "2") (pinfunction "2_2") (pintype "passive"))
      (node (ref "U$10") (pin "21") (pinfunction "BOOT_21") (pintype "bidirectional"))
    )
    (net (code "69") (name "Net-(U$10-ISET)") (class "Default")
      (node (ref "R21") (pin "2") (pinfunction "2_2") (pintype "passive"))
      (node (ref "U$10") (pin "10") (pinfunction "ISET_10") (pintype "bidirectional"))
    )
    (net (code "70") (name "Net-(U$10-PMID)") (class "Default")
      (node (ref "C22") (pin "1") (pinfunction "1_1") (pintype "passive"))
      (node (ref "U$10") (pin "20") (pinfunction "PMID_20") (pintype "bidirectional"))
    )
    (net (code "71") (name "Net-(U$10-TS)") (class "Default")
      (node (ref "R24") (pin "2") (pinfunction "2_2") (pintype "passive"))
      (node (ref "U$10") (pin "9") (pinfunction "TS_9") (pintype "bidirectional"))
    )
    (net (code "72") (name "Net-(U$10-{slash}CE)") (class "Default")
      (node (ref "R20") (pin "2") (pinfunction "2_2") (pintype "passive"))
      (node (ref "U$10") (pin "1") (pinfunction "/CE_1") (pintype "bidirectional"))
    )
    (net (code "73") (name "Net-(U$10-{slash}CHG)") (class "Default")
      (node (ref "R8") (pin "1") (pinfunction "1_1") (pintype "passive"))
      (node (ref "U$10") (pin "7") (pinfunction "/CHG_7") (pintype "bidirectional"))
    )
    (net (code "74") (name "Net-(U$11-MODE)") (class "Default")
      (node (ref "R5") (pin "2") (pinfunction "2_2") (pintype "passive"))
      (node (ref "U$11") (pin "16") (pinfunction "MODE_16") (pintype "bidirectional"))
    )
    (net (code "75") (name "Net-(U$11-OUT1)") (class "Default")
      (node (ref "U$11") (pin "10") (pinfunction "OUT1_10") (pintype "bidirectional"))
      (node (ref "U$13") (pin "P$2") (pinfunction "P$2_P$2") (pintype "bidirectional"))
    )
    (net (code "76") (name "Net-(U$11-OUT2)") (class "Default")
      (node (ref "U$11") (pin "9") (pinfunction "OUT2_9") (pintype "bidirectional"))
      (node (ref "U$13") (pin "P$1") (pinfunction "P$1_P$1") (pintype "bidirectional"))
    )
    (net (code "77") (name "Net-(U$11-OUT3)") (class "Default")
      (node (ref "U$11") (pin "11") (pinfunction "OUT3_11") (pintype "bidirectional"))
      (node (ref "U$13") (pin "P$3") (pinfunction "P$3_P$3") (pintype "bidirectional"))
    )
    (net (code "78") (name "Net-(U$11-OUT4)") (class "Default")
      (node (ref "U$11") (pin "12") (pinfunction "OUT4_12") (pintype "bidirectional"))
      (node (ref "U$13") (pin "P$4") (pinfunction "P$4_P$4") (pintype "bidirectional"))
    )
    (net (code "79") (name "Net-(U$12-MODE)") (class "Default")
      (node (ref "R1") (pin "2") (pinfunction "2_2") (pintype "passive"))
      (node (ref "U$12") (pin "16") (pinfunction "MODE_16") (pintype "bidirectional"))
    )
    (net (code "80") (name "Net-(U$12-OUT1)") (class "Default")
      (node (ref "U$12") (pin "10") (pinfunction "OUT1_10") (pintype "bidirectional"))
      (node (ref "U$17") (pin "P$2") (pinfunction "P$2_P$2") (pintype "bidirectional"))
    )
    (net (code "81") (name "Net-(U$12-OUT2)") (class "Default")
      (node (ref "U$12") (pin "9") (pinfunction "OUT2_9") (pintype "bidirectional"))
      (node (ref "U$17") (pin "P$1") (pinfunction "P$1_P$1") (pintype "bidirectional"))
    )
    (net (code "82") (name "Net-(U$12-OUT3)") (class "Default")
      (node (ref "U$12") (pin "11") (pinfunction "OUT3_11") (pintype "bidirectional"))
      (node (ref "U$17") (pin "P$3") (pinfunction "P$3_P$3") (pintype "bidirectional"))
    )
    (net (code "83") (name "Net-(U$12-OUT4)") (class "Default")
      (node (ref "U$12") (pin "12") (pinfunction "OUT4_12") (pintype "bidirectional"))
      (node (ref "U$17") (pin "P$4") (pinfunction "P$4_P$4") (pintype "bidirectional"))
    )
    (net (code "84") (name "Net-(U$16B-2)") (class "Default")
      (node (ref "BTN_USR1") (pin "P$1") (pinfunction "P$1_P$1") (pintype "bidirectional"))
      (node (ref "BTN_USR1") (pin "P$4") (pinfunction "P$1_P$4") (pintype "bidirectional"))
      (node (ref "U$16") (pin "7") (pinfunction "2_7") (pintype "passive"))
    )
    (net (code "85") (name "Net-(U$16D-1)") (class "Default")
      (node (ref "BTN_USR") (pin "P$1") (pinfunction "P$1_P$1") (pintype "bidirectional"))
      (node (ref "BTN_USR") (pin "P$4") (pinfunction "P$1_P$4") (pintype "bidirectional"))
      (node (ref "U$16") (pin "4") (pinfunction "1_4") (pintype "passive"))
    )
    (net (code "86") (name "Net-(U$26C-2)") (class "Default")
      (node (ref "U$26") (pin "6") (pinfunction "2_6") (pintype "passive"))
      (node (ref "U$8") (pin "5") (pinfunction "SDO_5") (pintype "bidirectional"))
    )
    (net (code "87") (name "PWM_1") (class "Default")
      (node (ref "U$1") (pin "27") (pinfunction "PB1_27") (pintype "bidirectional"))
      (node (ref "U$12") (pin "2") (pinfunction "EN_B_2") (pintype "bidirectional"))
      (node (ref "X1") (pin "20") (pinfunction "1_20") (pintype "passive"))
    )
    (net (code "88") (name "PWM_2") (class "Default")
      (node (ref "U$1") (pin "26") (pinfunction "PB0_26") (pintype "bidirectional"))
      (node (ref "U$12") (pin "4") (pinfunction "EN_A_4") (pintype "bidirectional"))
      (node (ref "X1") (pin "19") (pinfunction "1_19") (pintype "passive"))
    )
    (net (code "89") (name "PWM_3") (class "Default")
      (node (ref "U$1") (pin "37") (pinfunction "PC6_37") (pintype "bidirectional"))
      (node (ref "U$11") (pin "2") (pinfunction "EN_B_2") (pintype "bidirectional"))
    )
    (net (code "90") (name "PWM_4") (class "Default")
      (node (ref "U$1") (pin "38") (pinfunction "PC7_38") (pintype "bidirectional"))
      (node (ref "U$11") (pin "4") (pinfunction "EN_A_4") (pintype "bidirectional"))
    )
    (net (code "91") (name "P_EN_3") (class "Default")
      (node (ref "U$1") (pin "35") (pinfunction "PB14_35") (pintype "bidirectional"))
      (node (ref "U$11") (pin "5") (pinfunction "PH_A_5") (pintype "bidirectional"))
    )
    (net (code "92") (name "P_EN_4") (class "Default")
      (node (ref "U$1") (pin "36") (pinfunction "PB15_36") (pintype "bidirectional"))
      (node (ref "U$11") (pin "1") (pinfunction "PH_B_1") (pintype "bidirectional"))
    )
    (net (code "93") (name "SWCLK") (class "Default")
      (node (ref "U$1") (pin "49") (pinfunction "PA14_49") (pintype "bidirectional"))
      (node (ref "U$25") (pin "P$3") (pinfunction "P$3_P$3") (pintype "bidirectional"))
    )
    (net (code "94") (name "SWDIO") (class "Default")
      (node (ref "U$1") (pin "46") (pinfunction "PA13_46") (pintype "bidirectional"))
      (node (ref "U$25") (pin "P$2") (pinfunction "P$2_P$2") (pintype "bidirectional"))
    )
    (net (code "95") (name "UART2_RX") (class "Default")
      (node (ref "U$1") (pin "17") (pinfunction "PA3_17") (pintype "bidirectional"))
      (node (ref "U$20") (pin "P$3") (pinfunction "P$3_P$3") (pintype "bidirectional"))
      (node (ref "X1") (pin "6") (pinfunction "1_6") (pintype "passive"))
    )
    (net (code "96") (name "UART2_TX") (class "Default")
      (node (ref "U$1") (pin "16") (pinfunction "PA2_16") (pintype "bidirectional"))
      (node (ref "U$19") (pin "P$3") (pinfunction "P$3_P$3") (pintype "bidirectional"))
      (node (ref "X1") (pin "5") (pinfunction "1_5") (pintype "passive"))
    )
    (net (code "97") (name "UART4_RX") (class "Default")
      (node (ref "U$1") (pin "15") (pinfunction "PA1_15") (pintype "bidirectional"))
      (node (ref "X1") (pin "4") (pinfunction "1_4") (pintype "passive"))
    )
    (net (code "98") (name "UART4_TX") (class "Default")
      (node (ref "U$1") (pin "14") (pinfunction "PA0_14") (pintype "bidirectional"))
      (node (ref "X1") (pin "3") (pinfunction "1_3") (pintype "passive"))
    )
    (net (code "99") (name "USB_D+") (class "Default")
      (node (ref "U$1") (pin "45") (pinfunction "PA12_45") (pintype "bidirectional"))
      (node (ref "U$10") (pin "2") (pinfunction "D+_2") (pintype "bidirectional"))
      (node (ref "U$25") (pin "P$4") (pinfunction "P$4_P$4") (pintype "bidirectional"))
      (node (ref "U$7") (pin "A6") (pinfunction "D+_A6") (pintype "bidirectional"))
      (node (ref "U$7") (pin "B6") (pinfunction "D+_B6") (pintype "bidirectional"))
    )
    (net (code "100") (name "USB_D-") (class "Default")
      (node (ref "U$1") (pin "44") (pinfunction "PA11_44") (pintype "bidirectional"))
      (node (ref "U$10") (pin "3") (pinfunction "D-_3") (pintype "bidirectional"))
      (node (ref "U$25") (pin "P$5") (pinfunction "P$5_P$5") (pintype "bidirectional"))
      (node (ref "U$7") (pin "A7") (pinfunction "D-_A7") (pintype "bidirectional"))
      (node (ref "U$7") (pin "B7") (pinfunction "D-_B7") (pintype "bidirectional"))
    )
    (net (code "101") (name "USB_VBUS") (class "Default")
      (node (ref "U$10") (pin "19") (pinfunction "IN_19") (pintype "bidirectional"))
      (node (ref "U$7") (pin "A4") (pinfunction "VBUS_A4") (pintype "bidirectional"))
      (node (ref "U$7") (pin "A9") (pinfunction "VBUS_A9") (pintype "bidirectional"))
      (node (ref "U$7") (pin "B4") (pinfunction "VBUS_B4") (pintype "bidirectional"))
      (node (ref "U$7") (pin "B9") (pinfunction "VBUS_B9") (pintype "bidirectional"))
    )
    (net (code "102") (name "VBACKUP") (class "Default")
      (node (ref "C0") (pin "1") (pinfunction "1_1") (pintype "passive"))
      (node (ref "CBK") (pin "P$1") (pinfunction "1_P$1") (pintype "passive"))
      (node (ref "R6") (pin "1") (pinfunction "1_1") (pintype "passive"))
      (node (ref "U$1") (pin "1") (pinfunction "VBAT_1") (pintype "bidirectional"))
      (node (ref "U$3") (pin "5") (pinfunction "VBCK_5") (pintype "bidirectional"))
    )
    (net (code "103") (name "VCC") (class "Default")
      (node (ref "BTN_DFU") (pin "P$2") (pinfunction "P$2_P$2") (pintype "bidirectional"))
      (node (ref "C1") (pin "1") (pinfunction "1_1") (pintype "passive"))
      (node (ref "C16") (pin "2") (pinfunction "2_2") (pintype "passive"))
      (node (ref "C3") (pin "1") (pinfunction "1_1") (pintype "passive"))
      (node (ref "C31") (pin "1") (pinfunction "1_1") (pintype "passive"))
      (node (ref "C32") (pin "1") (pinfunction "1_1") (pintype "passive"))
      (node (ref "C4") (pin "1") (pinfunction "1_1") (pintype "passive"))
      (node (ref "C5") (pin "2") (pinfunction "2_2") (pintype "passive"))
      (node (ref "C50") (pin "1") (pinfunction "1_1") (pintype "passive"))
      (node (ref "C71") (pin "1") (pinfunction "1_1") (pintype "passive"))
      (node (ref "C72") (pin "1") (pinfunction "1_1") (pintype "passive"))
      (node (ref "C80") (pin "1") (pinfunction "1_1") (pintype "passive"))
      (node (ref "D1") (pin "1") (pinfunction "P$1_1") (pintype "bidirectional"))
      (node (ref "F1") (pin "1") (pinfunction "P$1_1") (pintype "bidirectional"))
      (node (ref "LEDP") (pin "A") (pinfunction "P$1_A") (pintype "bidirectional"))
      (node (ref "LM3940IMP") (pin "3") (pinfunction "VOUT_3") (pintype "bidirectional"))
      (node (ref "R4") (pin "1") (pinfunction "1_1") (pintype "passive"))
      (node (ref "U$1") (pin "19") (pinfunction "VDD_19") (pintype "bidirectional"))
      (node (ref "U$1") (pin "32") (pinfunction "VDD_32") (pintype "bidirectional"))
      (node (ref "U$1") (pin "48") (pinfunction "VDD_48") (pintype "bidirectional"))
      (node (ref "U$1") (pin "64") (pinfunction "VDD_64") (pintype "bidirectional"))
      (node (ref "U$15") (pin "1") (pinfunction "1_1") (pintype "passive"))
      (node (ref "U$15") (pin "2") (pinfunction "1_2") (pintype "passive"))
      (node (ref "U$15") (pin "3") (pinfunction "1_3") (pintype "passive"))
      (node (ref "U$15") (pin "4") (pinfunction "1_4") (pintype "passive"))
      (node (ref "U$16") (pin "1") (pinfunction "1_1") (pintype "passive"))
      (node (ref "U$16") (pin "2") (pinfunction "1_2") (pintype "passive"))
      (node (ref "U$16") (pin "5") (pinfunction "2_5") (pintype "passive"))
      (node (ref "U$2") (pin "VCC") (pinfunction "VDD_VCC") (pintype "bidirectional"))
      (node (ref "U$21") (pin "3") (pinfunction "VCC_3") (pintype "bidirectional"))
      (node (ref "U$25") (pin "P$6") (pinfunction "P$6_P$6") (pintype "bidirectional"))
      (node (ref "U$26") (pin "1") (pinfunction "1_1") (pintype "passive"))
      (node (ref "U$26") (pin "2") (pinfunction "1_2") (pintype "passive"))
      (node (ref "U$26") (pin "3") (pinfunction "1_3") (pintype "passive"))
      (node (ref "U$26") (pin "4") (pinfunction "1_4") (pintype "passive"))
      (node (ref "U$3") (pin "4") (pinfunction "VCC_4") (pintype "bidirectional"))
      (node (ref "U$8") (pin "6") (pinfunction "VDDIO_6") (pintype "bidirectional"))
      (node (ref "U$8") (pin "8") (pinfunction "VDD_8") (pintype "bidirectional"))
      (node (ref "U$9") (pin "1") (pinfunction "RESV1_1") (pintype "bidirectional"))
      (node (ref "U$9") (pin "13") (pinfunction "VDD_13") (pintype "bidirectional"))
      (node (ref "U$9") (pin "8") (pinfunction "VDDIO_8") (pintype "bidirectional"))
      (node (ref "X1") (pin "17") (pinfunction "1_17") (pintype "passive"))
      (node (ref "X1") (pin "2") (pinfunction "1_2") (pintype "passive"))
      (node (ref "X1") (pin "23") (pinfunction "1_23") (pintype "passive"))
      (node (ref "X1") (pin "8") (pinfunction "1_8") (pintype "passive"))
    )
    (net (code "104") (name "VSYS") (class "Default")
      (node (ref "C24") (pin "1") (pinfunction "1_1") (pintype "passive"))
      (node (ref "C30") (pin "1") (pinfunction "1_1") (pintype "passive"))
      (node (ref "L2") (pin "P$2") (pinfunction "P$2_P$2") (pintype "bidirectional"))
      (node (ref "LEDCH") (pin "A") (pinfunction "P$1_A") (pintype "bidirectional"))
      (node (ref "LM3940IMP") (pin "1") (pinfunction "VIN_1") (pintype "bidirectional"))
      (node (ref "U$10") (pin "13") (pinfunction "SYS_13") (pintype "bidirectional"))
      (node (ref "U$10") (pin "14") (pinfunction "SYS_14") (pintype "bidirectional"))
      (node (ref "U$14") (pin "AUX") (pinfunction "AUX+_AUX") (pintype "bidirectional"))
    )
    (net (code "105") (name "unconnected-(BTN_DFU-PadP$1)") (class "Default")
      (node (ref "BTN_DFU") (pin "P$1") (pinfunction "P$1_P$1") (pintype "bidirectional"))
    )
    (net (code "106") (name "unconnected-(U$3-ANT-Pad11)") (class "Default")
      (node (ref "U$3") (pin "11") (pinfunction "ANT_11") (pintype "bidirectional"))
    )
    (net (code "107") (name "unconnected-(U$9B-P4-Pad4)") (class "Default")
      (node (ref "U$9") (pin "4") (pinfunction "P4_4") (pintype "bidirectional"))
    )
    (net (code "108") (name "unconnected-(U$9B-P6-Pad6)") (class "Default")
      (node (ref "U$9") (pin "6") (pinfunction "P6_6") (pintype "bidirectional"))
    )
    (net (code "109") (name "unconnected-(U$9B-P16-Pad16)") (class "Default")
      (node (ref "U$9") (pin "16") (pinfunction "P16_16") (pintype "bidirectional"))
    )
    (net (code "110") (name "unconnected-(U$9B-P17-Pad17)") (class "Default")
      (node (ref "U$9") (pin "17") (pinfunction "P17_17") (pintype "bidirectional"))
    )
    (net (code "111") (name "unconnected-(U$10-EN1-Pad5)") (class "Default")
      (node (ref "U$10") (pin "5") (pinfunction "EN1_5") (pintype "bidirectional"))
    )
    (net (code "112") (name "unconnected-(U$10-EN2-Pad6)") (class "Default")
      (node (ref "U$10") (pin "6") (pinfunction "EN2_6") (pintype "bidirectional"))
    )
    (net (code "113") (name "unconnected-(U$10-{slash}PG-Pad8)") (class "Default")
      (node (ref "U$10") (pin "8") (pinfunction "/PG_8") (pintype "bidirectional"))
    )
    (net (code "114") (name "unconnected-(U$21-GND{slash}D4-Pad10)") (class "Default")
      (node (ref "U$21") (pin "10") (pinfunction "GND/D4_10") (pintype "bidirectional"))
    )
    (net (code "115") (name "unconnected-(U$21-GND{slash}D5-Pad11)") (class "Default")
      (node (ref "U$21") (pin "11") (pinfunction "GND/D5_11") (pintype "bidirectional"))
    )
    (net (code "116") (name "unconnected-(U$21-NSS{slash}D3-Pad8)") (class "Default")
      (node (ref "U$21") (pin "8") (pinfunction "NSS/D3_8") (pintype "bidirectional"))
    )
    (net (code "117") (name "unconnected-(U$21-SCK{slash}D2-Pad7)") (class "Default")
      (node (ref "U$21") (pin "7") (pinfunction "SCK/D2_7") (pintype "bidirectional"))
    )
  )
)
